# DUAL_CHANNEL_REAY_DRIVER.net
KiCad netlist of a schematic drawn in EAGLE
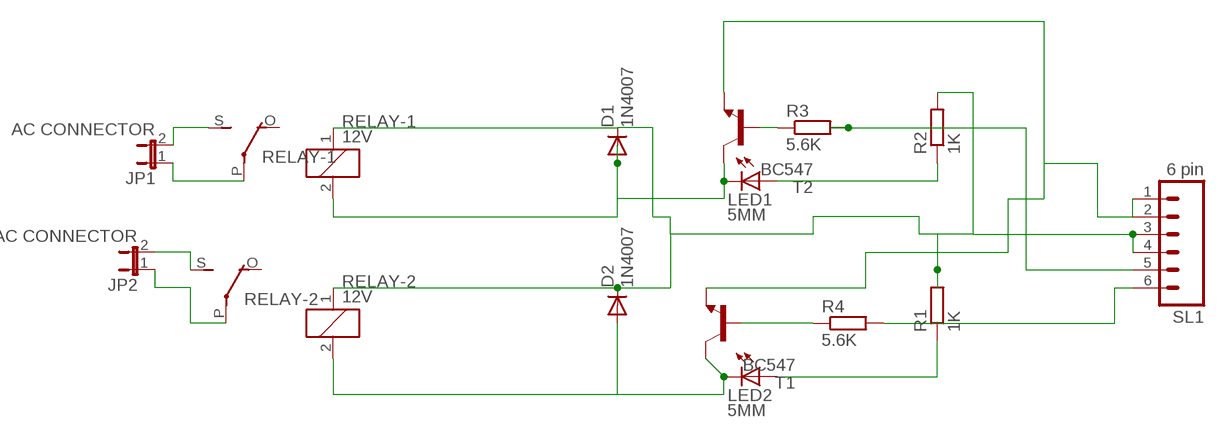
[diagram p0: schematic, sheet 1]

(export (version "E")
  (design (tool "Eeschema 10.0.6"))
  (components
    (comp (ref "D1")
      (value "1N4007")
      (footprint "eagle-import:DO41-10")
      (libsource (lib "eagle-import") (part "1N4004"))
    )
    (comp (ref "D2")
      (value "1N4007")
      (footprint "eagle-import:DO41-10")
      (libsource (lib "eagle-import") (part "1N4004"))
    )
    (comp (ref "JP1")
      (value "AC CONNECTOR")
      (footprint "eagle-import:JP1")
      (libsource (lib "eagle-import") (part "JP1E"))
    )
    (comp (ref "JP2")
      (value "AC CONNECTOR")
      (footprint "eagle-import:JP1")
      (libsource (lib "eagle-import") (part "JP1E"))
    )
    (comp (ref "LED1")
      (value "5MM")
      (footprint "eagle-import:LED5MM")
      (libsource (lib "eagle-import") (part "LED5MM"))
    )
    (comp (ref "LED2")
      (value "5MM")
      (footprint "eagle-import:LED5MM")
      (libsource (lib "eagle-import") (part "LED5MM"))
    )
    (comp (ref "R1")
      (value "1K")
      (footprint "eagle-import:0204_7")
      (libsource (lib "eagle-import") (part "R-EU_0204/7"))
    )
    (comp (ref "R2")
      (value "1K")
      (footprint "eagle-import:0204_7")
      (libsource (lib "eagle-import") (part "R-EU_0204/7"))
    )
    (comp (ref "R3")
      (value "5.6K")
      (footprint "eagle-import:0204_7")
      (libsource (lib "eagle-import") (part "R-EU_0204/7"))
    )
    (comp (ref "R4")
      (value "5.6K")
      (footprint "eagle-import:0204_7")
      (libsource (lib "eagle-import") (part "R-EU_0204/7"))
    )
    (comp (ref "RELAY-1")
      (value "12V")
      (footprint "eagle-import:G5LE")
      (libsource (lib "eagle-import") (part "G5L"))
    )
    (comp (ref "RELAY-2")
      (value "12V")
      (footprint "eagle-import:G5LE")
      (libsource (lib "eagle-import") (part "G5L"))
    )
    (comp (ref "SL1")
      (value "6 pin")
      (footprint "eagle-import:06P")
      (libsource (lib "eagle-import") (part "M06"))
    )
    (comp (ref "T1")
      (value "BC547")
      (footprint "eagle-import:TO92")
      (libsource (lib "eagle-import") (part "BC547"))
    )
    (comp (ref "T2")
      (value "BC547")
      (footprint "eagle-import:TO92")
      (libsource (lib "eagle-import") (part "BC547"))
    )
  )
  (nets
    (net (code "1") (name "Net-(D1-PadC)") (class "Default")
      (node (ref "D1") (pin "C") (pinfunction "C_C") (pintype "passive"))
      (node (ref "D2") (pin "C") (pinfunction "C_C") (pintype "passive"))
      (node (ref "R1") (pin "2") (pinfunction "2_2") (pintype "passive"))
      (node (ref "R2") (pin "2") (pinfunction "2_2") (pintype "passive"))
      (node (ref "RELAY-1") (pin "1") (pinfunction "1_1") (pintype "passive"))
      (node (ref "RELAY-2") (pin "1") (pinfunction "1_1") (pintype "passive"))
      (node (ref "SL1") (pin "3") (pinfunction "3_3") (pintype "passive"))
      (node (ref "SL1") (pin "4") (pinfunction "4_4") (pintype "passive"))
    )
    (net (code "2") (name "Net-(JP1-Pad1)") (class "Default")
      (node (ref "JP1") (pin "1") (pinfunction "1_1") (pintype "passive"))
      (node (ref "RELAY-1") (pin "P") (pinfunction "P_P") (pintype "passive"))
    )
    (net (code "3") (name "Net-(JP1-Pad2)") (class "Default")
      (node (ref "JP1") (pin "2") (pinfunction "2_2") (pintype "passive"))
      (node (ref "RELAY-1") (pin "S") (pinfunction "S_S") (pintype "passive"))
    )
    (net (code "4") (name "Net-(JP2-Pad1)") (class "Default")
      (node (ref "JP2") (pin "1") (pinfunction "1_1") (pintype "passive"))
      (node (ref "RELAY-2") (pin "P") (pinfunction "P_P") (pintype "passive"))
    )
    (net (code "5") (name "Net-(JP2-Pad2)") (class "Default")
      (node (ref "JP2") (pin "2") (pinfunction "2_2") (pintype "passive"))
      (node (ref "RELAY-2") (pin "S") (pinfunction "S_S") (pintype "passive"))
    )
    (net (code "6") (name "Net-(LED1-C)") (class "Default")
      (node (ref "D1") (pin "A") (pinfunction "A_A") (pintype "passive"))
      (node (ref "LED1") (pin "K") (pinfunction "C_K") (pintype "passive"))
      (node (ref "RELAY-1") (pin "2") (pinfunction "2_2") (pintype "passive"))
      (node (ref "T2") (pin "3") (pinfunction "C_3") (pintype "passive"))
    )
    (net (code "7") (name "Net-(LED1-PadA)") (class "Default")
      (node (ref "LED1") (pin "A") (pinfunction "A_A") (pintype "passive"))
      (node (ref "R2") (pin "1") (pinfunction "1_1") (pintype "passive"))
    )
    (net (code "8") (name "Net-(LED2-C)") (class "Default")
      (node (ref "D2") (pin "A") (pinfunction "A_A") (pintype "passive"))
      (node (ref "LED2") (pin "K") (pinfunction "C_K") (pintype "passive"))
      (node (ref "RELAY-2") (pin "2") (pinfunction "2_2") (pintype "passive"))
      (node (ref "T1") (pin "3") (pinfunction "C_3") (pintype "passive"))
    )
    (net (code "9") (name "Net-(LED2-PadA)") (class "Default")
      (node (ref "LED2") (pin "A") (pinfunction "A_A") (pintype "passive"))
      (node (ref "R1") (pin "1") (pinfunction "1_1") (pintype "passive"))
    )
    (net (code "10") (name "Net-(R3-Pad2)") (class "Default")
      (node (ref "R3") (pin "2") (pinfunction "2_2") (pintype "passive"))
      (node (ref "SL1") (pin "5") (pinfunction "5_5") (pintype "passive"))
    )
    (net (code "11") (name "Net-(R4-Pad2)") (class "Default")
      (node (ref "R4") (pin "2") (pinfunction "2_2") (pintype "passive"))
      (node (ref "SL1") (pin "6") (pinfunction "6_6") (pintype "passive"))
    )
    (net (code "12") (name "Net-(T1-B)") (class "Default")
      (node (ref "R4") (pin "1") (pinfunction "1_1") (pintype "passive"))
      (node (ref "T1") (pin "2") (pinfunction "B_2") (pintype "passive"))
    )
    (net (code "13") (name "Net-(T1-E)") (class "Default")
      (node (ref "SL1") (pin "1") (pinfunction "1_1") (pintype "passive"))
      (node (ref "SL1") (pin "2") (pinfunction "2_2") (pintype "passive"))
      (node (ref "T1") (pin "1") (pinfunction "E_1") (pintype "passive"))
      (node (ref "T2") (pin "1") (pinfunction "E_1") (pintype "passive"))
    )
    (net (code "14") (name "Net-(T2-B)") (class "Default")
      (node (ref "R3") (pin "1") (pinfunction "1_1") (pintype "passive"))
      (node (ref "T2") (pin "2") (pinfunction "B_2") (pintype "passive"))
    )
    (net (code "15") (name "unconnected-(RELAY-1-PadO)") (class "Default")
      (node (ref "RELAY-1") (pin "O") (pinfunction "O_O") (pintype "passive"))
    )
    (net (code "16") (name "unconnected-(RELAY-2-PadO)") (class "Default")
      (node (ref "RELAY-2") (pin "O") (pinfunction "O_O") (pintype "passive"))
    )
  )
)
